# Flash.net
KiCad netlist of a schematic drawn in Altium Designer
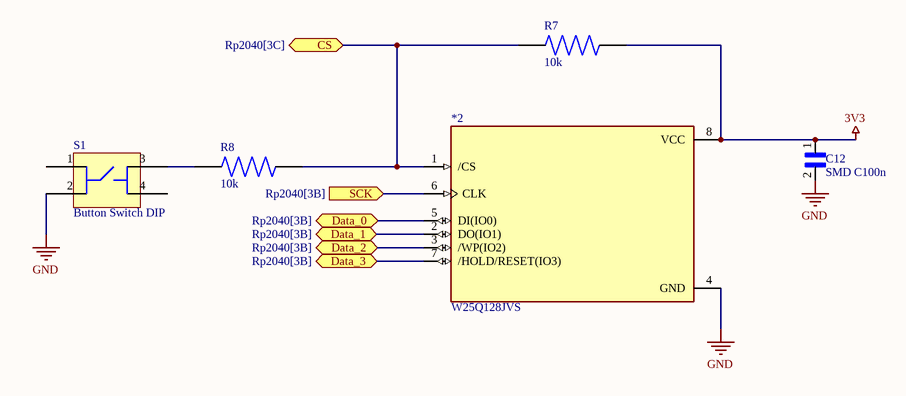
[diagram p0: Flash.SchDoc]

(export (version "E")
  (design (tool "Eeschema 10.0.6"))
  (components
    (comp (ref "*2")
      (value "W25Q128JVS")
      (footprint "W25Q128JVS-Footprint-1")
      (description "Flash Memory")
      (libsource (lib "Tobias") (part "W25Q128JVS-Symbol-1"))
    )
    (comp (ref "C12")
      (value "SMD C100n")
      (footprint "SMD Capacetor-Footprint-1")
      (description "Generic SMD Capacetor")
      (libsource (lib "Tobias") (part "100n"))
    )
    (comp (ref "R7")
      (value "10k")
      (footprint "SMD Resistor-Footprint-1")
      (description "Generic SMD Resistor")
      (libsource (lib "Tobias") (part "SMD Resistor-Symbol-1"))
    )
    (comp (ref "R8")
      (value "10k")
      (footprint "SMD Resistor-Footprint-1")
      (description "Generic SMD Resistor")
      (libsource (lib "Tobias") (part "SMD Resistor-Symbol-1"))
    )
    (comp (ref "S1")
      (value "Button Switch DIP")
      (footprint "Button Switch DIP -Footprint-1")
      (description "4 Pin")
      (libsource (lib "Tobias") (part "Button Switch DIP -Symbol-1"))
    )
  )
  (nets
    (net (code "1") (name "/CS") (class "Default")
      (node (ref "*2") (pin "1") (pinfunction "/CS_1") (pintype "input"))
      (node (ref "R7") (pin "1") (pinfunction "1_1") (pintype "passive"))
      (node (ref "R8") (pin "2") (pinfunction "2_2") (pintype "passive"))
    )
    (net (code "2") (name "/Data_0") (class "Default")
      (node (ref "*2") (pin "5") (pinfunction "DI(IO0)_5") (pintype "bidirectional"))
    )
    (net (code "3") (name "/Data_1") (class "Default")
      (node (ref "*2") (pin "2") (pinfunction "DO(IO1)_2") (pintype "bidirectional"))
    )
    (net (code "4") (name "/Data_2") (class "Default")
      (node (ref "*2") (pin "3") (pinfunction "/WP(IO2)_3") (pintype "bidirectional"))
    )
    (net (code "5") (name "/Data_3") (class "Default")
      (node (ref "*2") (pin "7") (pinfunction "/HOLD/RESET(IO3)_7") (pintype "bidirectional"))
    )
    (net (code "6") (name "/SCK") (class "Default")
      (node (ref "*2") (pin "6") (pinfunction "CLK_6") (pintype "input"))
    )
    (net (code "7") (name "3V3") (class "Default")
      (node (ref "*2") (pin "8") (pinfunction "VCC_8") (pintype "power_in"))
      (node (ref "C12") (pin "1") (pinfunction "1_1") (pintype "passive"))
      (node (ref "R7") (pin "2") (pinfunction "2_2") (pintype "passive"))
    )
    (net (code "8") (name "GND") (class "Default")
      (node (ref "*2") (pin "4") (pinfunction "GND_4") (pintype "power_in"))
      (node (ref "C12") (pin "2") (pinfunction "2_2") (pintype "passive"))
      (node (ref "S1") (pin "2") (pinfunction "2_2") (pintype "passive"))
    )
    (net (code "9") (name "Net-(R8-Pad1)") (class "Default")
      (node (ref "R8") (pin "1") (pinfunction "1_1") (pintype "passive"))
      (node (ref "S1") (pin "3") (pinfunction "3_3") (pintype "passive"))
    )
    (net (code "10") (name "unconnected-(S1-Pad1)") (class "Default")
      (node (ref "S1") (pin "1") (pinfunction "1_1") (pintype "passive"))
    )
    (net (code "11") (name "unconnected-(S1-Pad4)") (class "Default")
      (node (ref "S1") (pin "4") (pinfunction "4_4") (pintype "passive"))
    )
  )
)
